# RFM69_RPI_adapter.net
KiCad netlist of a schematic drawn in EAGLE
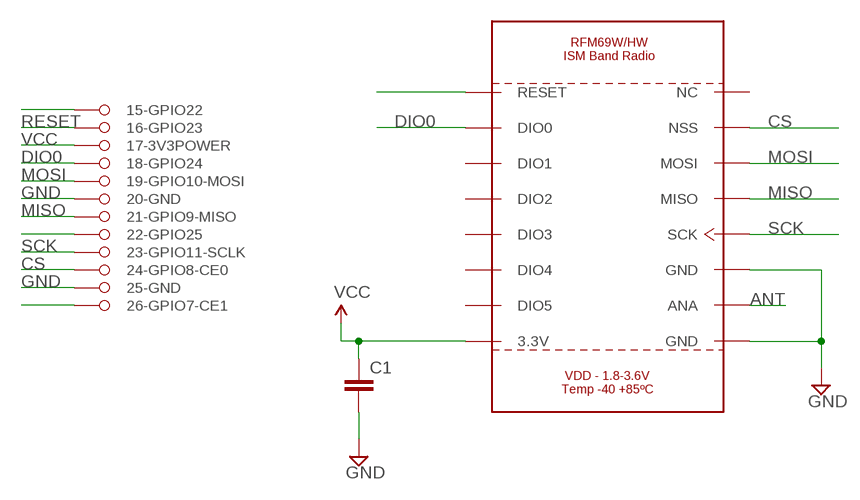
[diagram p0: schematic, sheet 1]

(export (version "E")
  (design (tool "Eeschema 10.0.6"))
  (components
    (comp (ref "C1")
      (value "C-EUC1206K")
      (footprint "eagle-import:C1206K")
      (libsource (lib "eagle-import") (part "C-EUC1206K"))
    )
    (comp (ref "U$1")
      (value "RFM69W/HW-")
      (footprint "eagle-import:RFM69W_HW")
      (libsource (lib "eagle-import") (part "RFM69W/HW-"))
    )
    (comp (ref "U$2")
      (value "RASPBPI_16-26")
      (footprint "eagle-import:RASPBP1_16-26")
      (libsource (lib "eagle-import") (part "RASPBPI_16-26"))
    )
  )
  (nets
    (net (code "1") (name "/ANT") (class "Default")
      (node (ref "U$1") (pin "P$10") (pinfunction "ANA_P$10") (pintype "bidirectional"))
    )
    (net (code "2") (name "/CS") (class "Default")
      (node (ref "U$1") (pin "P$15") (pinfunction "NSS_P$15") (pintype "bidirectional"))
      (node (ref "U$2") (pin "24-GPIO8-CE0") (pinfunction "24-GPIO8-CE0_24-GPIO8-CE0") (pintype "bidirectional"))
    )
    (net (code "3") (name "/DIO0") (class "Default")
      (node (ref "U$1") (pin "P$2") (pinfunction "DIO0_P$2") (pintype "bidirectional"))
      (node (ref "U$2") (pin "18-GPIO24") (pinfunction "18-GPIO24_18-GPIO24") (pintype "bidirectional"))
    )
    (net (code "4") (name "/MISO") (class "Default")
      (node (ref "U$1") (pin "P$13") (pinfunction "MISO_P$13") (pintype "bidirectional"))
      (node (ref "U$2") (pin "21-GPIO9-MISO") (pinfunction "21-GPIO9-MISO_21-GPIO9-MISO") (pintype "bidirectional"))
    )
    (net (code "5") (name "/MOSI") (class "Default")
      (node (ref "U$1") (pin "P$14") (pinfunction "MOSI_P$14") (pintype "bidirectional"))
      (node (ref "U$2") (pin "19-GPIO10-MOSI") (pinfunction "19-GPIO10-MOSI_19-GPIO10-MOSI") (pintype "bidirectional"))
    )
    (net (code "6") (name "/RESET") (class "Default")
      (node (ref "U$1") (pin "P$1") (pinfunction "RESET_P$1") (pintype "bidirectional"))
      (node (ref "U$2") (pin "16-GPIO23") (pinfunction "16-GPIO23_16-GPIO23") (pintype "bidirectional"))
    )
    (net (code "7") (name "/SCK") (class "Default")
      (node (ref "U$1") (pin "P$12") (pinfunction "SCK_P$12") (pintype "bidirectional"))
      (node (ref "U$2") (pin "23-GPIO11-SCKL") (pinfunction "23-GPIO11-SCLK_23-GPIO11-SCKL") (pintype "bidirectional"))
    )
    (net (code "8") (name "GND") (class "Default")
      (node (ref "C1") (pin "2") (pinfunction "2_2") (pintype "passive"))
      (node (ref "U$1") (pin "P$11") (pinfunction "GND_P$11") (pintype "power_in"))
      (node (ref "U$1") (pin "P$9") (pinfunction "GND_P$9") (pintype "power_in"))
      (node (ref "U$2") (pin "20-GND") (pinfunction "20-GND_20-GND") (pintype "bidirectional"))
      (node (ref "U$2") (pin "25-GND") (pinfunction "25-GND_25-GND") (pintype "bidirectional"))
    )
    (net (code "9") (name "VCC") (class "Default")
      (node (ref "C1") (pin "1") (pinfunction "1_1") (pintype "passive"))
      (node (ref "U$1") (pin "P$8") (pinfunction "3.3V_P$8") (pintype "power_in"))
      (node (ref "U$2") (pin "17-3V3POWER") (pinfunction "17-3V3POWER_17-3V3POWER") (pintype "bidirectional"))
    )
    (net (code "10") (name "unconnected-(U$1-DIO1-PadP$3)") (class "Default")
      (node (ref "U$1") (pin "P$3") (pinfunction "DIO1_P$3") (pintype "bidirectional"))
    )
    (net (code "11") (name "unconnected-(U$1-DIO2-PadP$4)") (class "Default")
      (node (ref "U$1") (pin "P$4") (pinfunction "DIO2_P$4") (pintype "bidirectional"))
    )
    (net (code "12") (name "unconnected-(U$1-DIO3-PadP$5)") (class "Default")
      (node (ref "U$1") (pin "P$5") (pinfunction "DIO3_P$5") (pintype "bidirectional"))
    )
    (net (code "13") (name "unconnected-(U$1-DIO4-PadP$6)") (class "Default")
      (node (ref "U$1") (pin "P$6") (pinfunction "DIO4_P$6") (pintype "bidirectional"))
    )
    (net (code "14") (name "unconnected-(U$1-DIO5-PadP$7)") (class "Default")
      (node (ref "U$1") (pin "P$7") (pinfunction "DIO5_P$7") (pintype "bidirectional"))
    )
    (net (code "15") (name "unconnected-(U$1-NC-PadP$16)") (class "Default")
      (node (ref "U$1") (pin "P$16") (pinfunction "NC_P$16") (pintype "no_connect"))
    )
    (net (code "16") (name "unconnected-(U$2-26-GPIO7-CE1-Pad26.GPIO6-CE1)") (class "Default")
      (node (ref "U$2") (pin "26.GPIO6-CE1") (pinfunction "26-GPIO7-CE1_26.GPIO6-CE1") (pintype "bidirectional"))
    )
    (net (code "17") (name "unconnected-(U$2-Pad15-GPIO22)") (class "Default")
      (node (ref "U$2") (pin "15-GPIO22") (pinfunction "15-GPIO22_15-GPIO22") (pintype "bidirectional"))
    )
    (net (code "18") (name "unconnected-(U$2-Pad22-GPIO25)") (class "Default")
      (node (ref "U$2") (pin "22-GPIO25") (pinfunction "22-GPIO25_22-GPIO25") (pintype "bidirectional"))
    )
  )
)
